# CR2032_Battery_Connector.net
KiCad netlist of a schematic drawn in Altium Designer
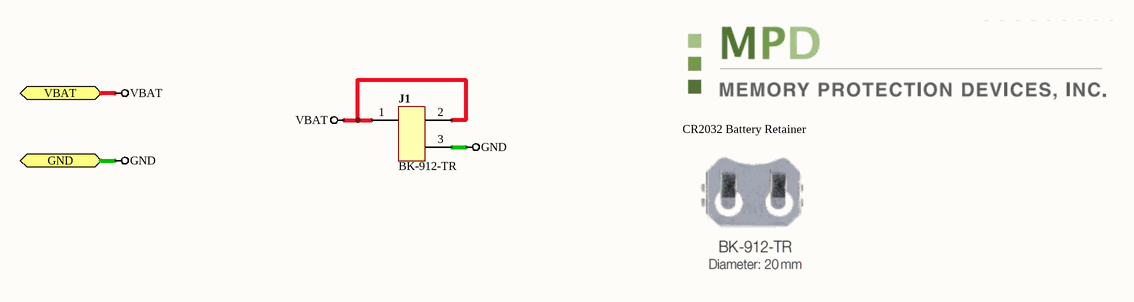
[diagram p0: CR2032_Battery_Connector.SchDoc]

(export (version "E")
  (design (tool "Eeschema 10.0.6"))
  (components
    (comp (ref "J1")
      (value "BK-912-TR")
      (footprint "MPD-CN-DIN-3_V")
      (description "Coin Cell Holder, 21.08 x 15.24 mm SMD")
      (fields (field (name "MANUFACTURER") "Memory Protection Devices"))
      (libsource (lib "Altium Content Vault") (part "MPD-BK-912-TR-3"))
    )
  )
  (nets
    (net (code "1") (name "GND") (class "Default")
      (node (ref "J1") (pin "3") (pinfunction "NEGATIVE_3") (pintype "passive"))
    )
    (net (code "2") (name "VBAT") (class "Default")
      (node (ref "J1") (pin "1") (pinfunction "POSITIVE_1") (pintype "passive"))
      (node (ref "J1") (pin "2") (pinfunction "POSITIVE_2") (pintype "passive"))
    )
  )
)
